# moire_v1_7.net
KiCad netlist of a schematic drawn in EAGLE
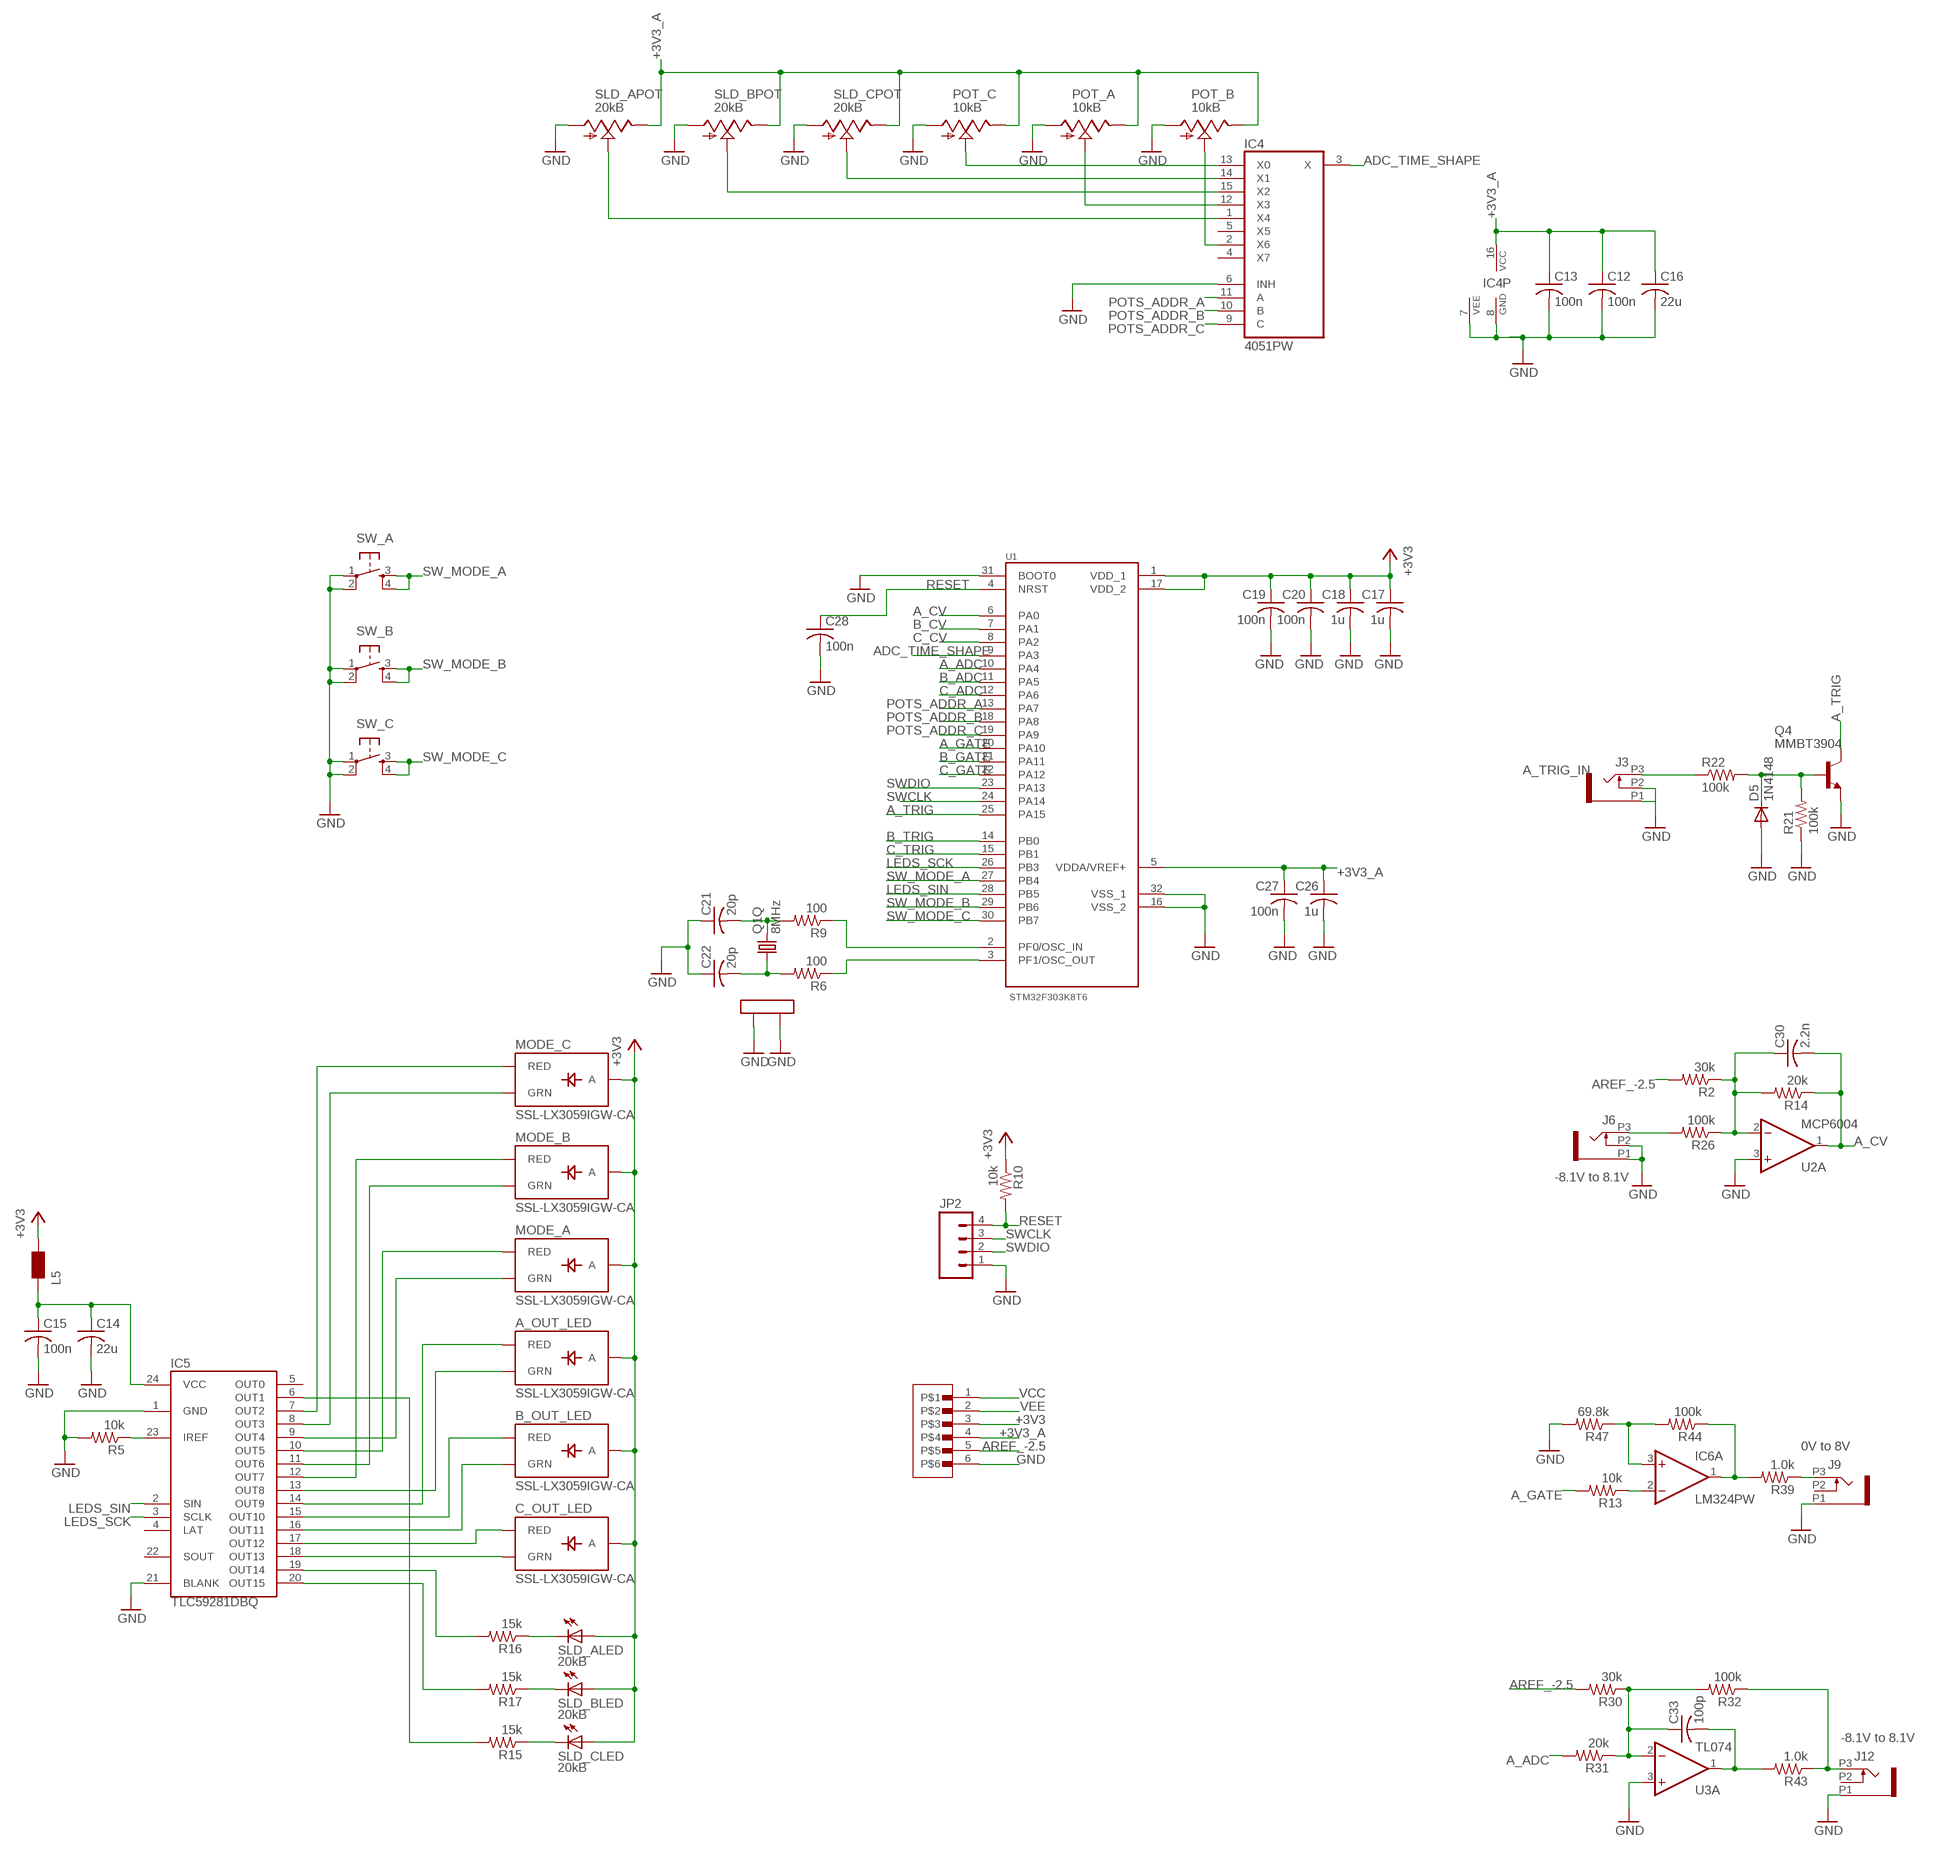
[diagram p0: schematic, sheet 1, part 1 of 2]
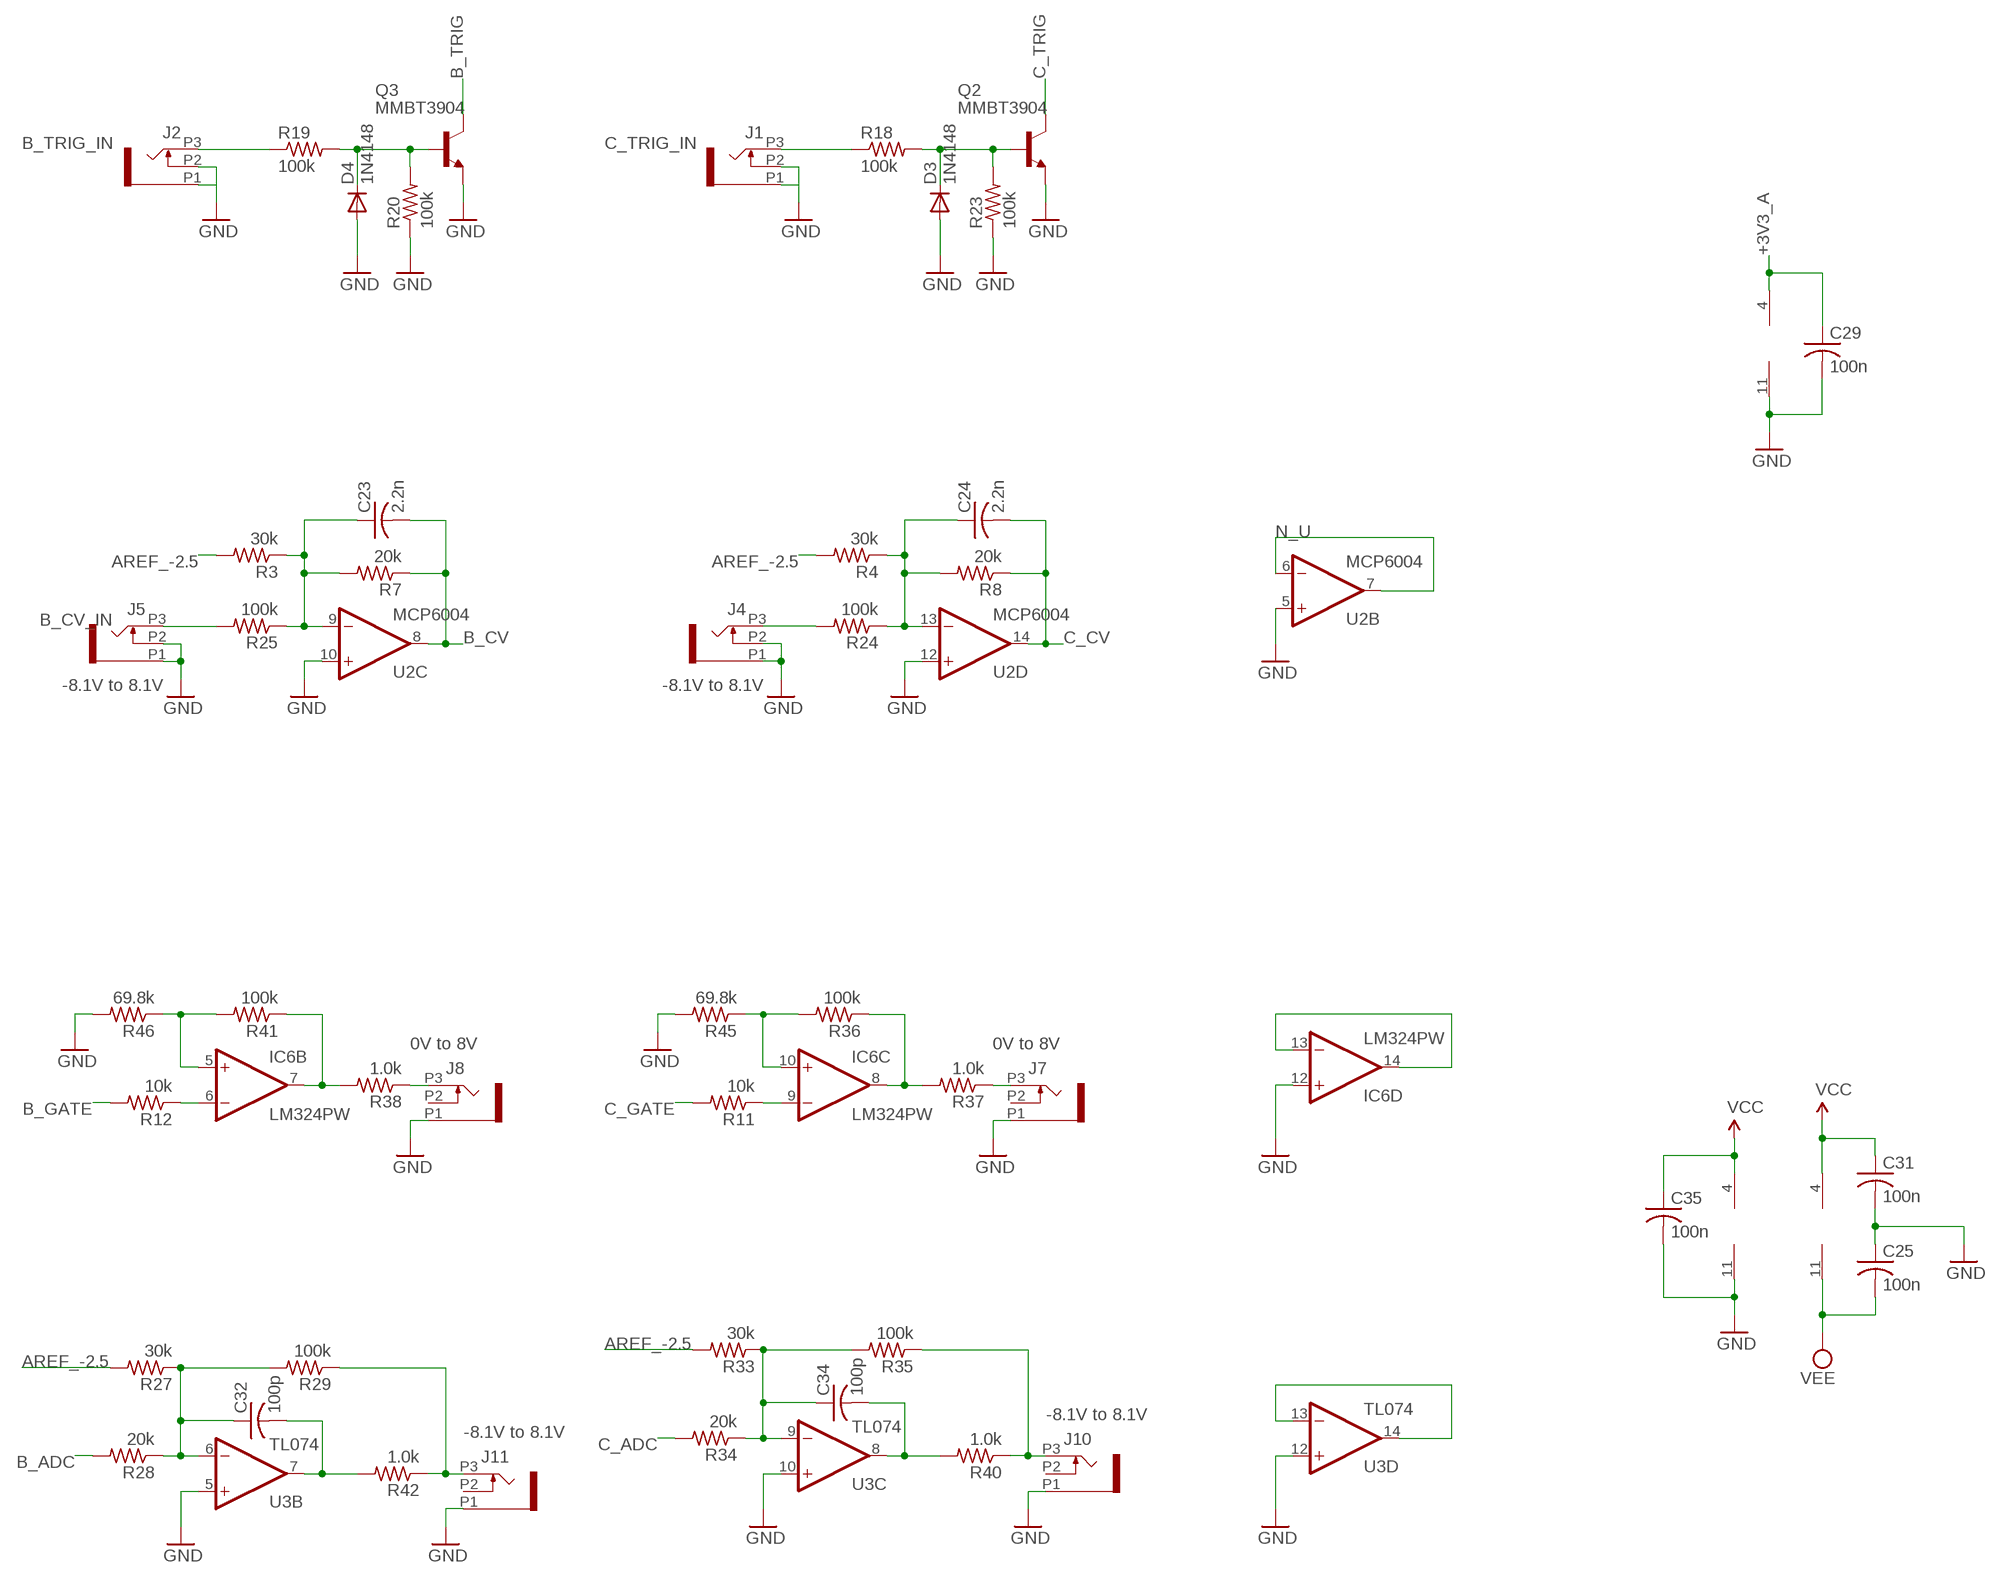
[diagram p1: schematic, sheet 1, part 2 of 2]
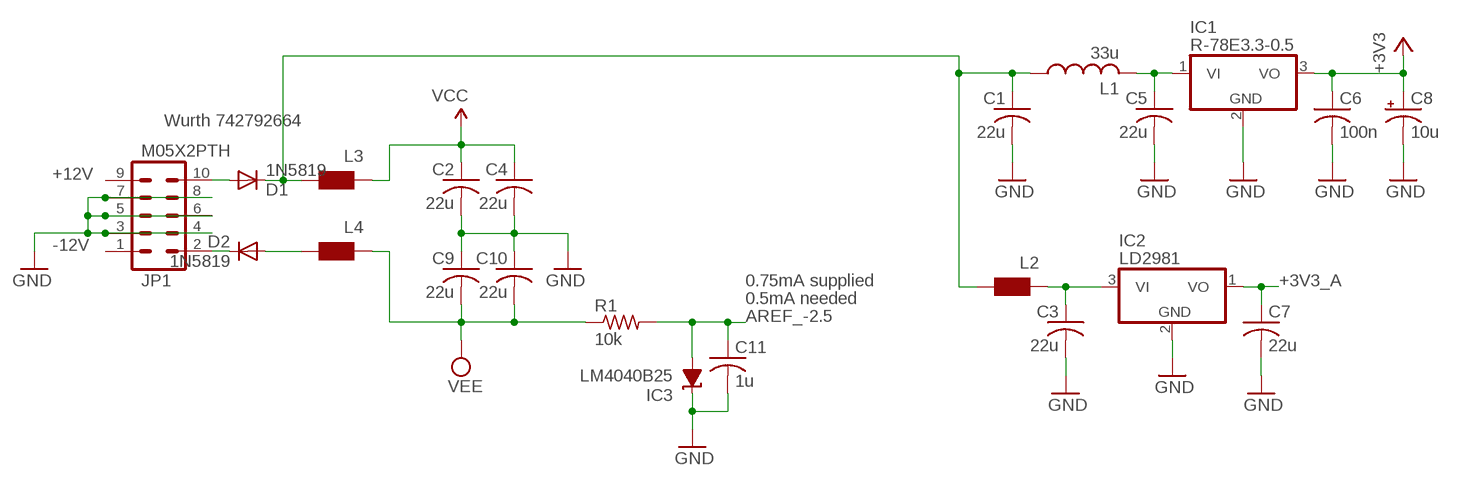
[diagram p2: schematic, sheet 2]

(export (version "E")
  (design (tool "Eeschema 10.0.6"))
  (components
    (comp (ref "C1")
      (value "22u")
      (footprint "eagle-import:RCL_C1206")
      (libsource (lib "eagle-import") (part "RCL_C-USC1206"))
    )
    (comp (ref "C2")
      (value "22u")
      (footprint "eagle-import:RCL_C1206")
      (libsource (lib "eagle-import") (part "RCL_C-USC1206"))
    )
    (comp (ref "C3")
      (value "22u")
      (footprint "eagle-import:RCL_C1206")
      (libsource (lib "eagle-import") (part "RCL_C-USC1206"))
    )
    (comp (ref "C4")
      (value "22u")
      (footprint "eagle-import:RCL_C1206")
      (libsource (lib "eagle-import") (part "RCL_C-USC1206"))
    )
    (comp (ref "C5")
      (value "22u")
      (footprint "eagle-import:RCL_C1206")
      (libsource (lib "eagle-import") (part "RCL_C-USC1206"))
    )
    (comp (ref "C6")
      (value "100n")
      (footprint "eagle-import:RCL_C0603")
      (libsource (lib "eagle-import") (part "RCL_C-USC0603"))
    )
    (comp (ref "C7")
      (value "22u")
      (footprint "eagle-import:RCL_C1206")
      (libsource (lib "eagle-import") (part "RCL_C-USC1206"))
    )
    (comp (ref "C8")
      (value "10u")
      (footprint "eagle-import:RCL_PANASONIC_A")
      (libsource (lib "eagle-import") (part "RCL_CPOL-USA"))
    )
    (comp (ref "C9")
      (value "22u")
      (footprint "eagle-import:RCL_C1206")
      (libsource (lib "eagle-import") (part "RCL_C-USC1206"))
    )
    (comp (ref "C10")
      (value "22u")
      (footprint "eagle-import:RCL_C1206")
      (libsource (lib "eagle-import") (part "RCL_C-USC1206"))
    )
    (comp (ref "C11")
      (value "1u")
      (footprint "eagle-import:RCL_C0603")
      (libsource (lib "eagle-import") (part "RCL_C-USC0603"))
    )
    (comp (ref "D1")
      (value "1N5819")
      (footprint "eagle-import:SOD123")
      (libsource (lib "eagle-import") (part "DIODE-SOD123"))
    )
    (comp (ref "D2")
      (value "1N5819")
      (footprint "eagle-import:SOD123")
      (libsource (lib "eagle-import") (part "DIODE-SOD123"))
    )
    (comp (ref "IC1")
      (value "R-78E3.3-0.5")
      (footprint "eagle-import:WE78")
      (libsource (lib "eagle-import") (part "WE173950378"))
    )
    (comp (ref "IC2")
      (value "LD2981")
      (footprint "eagle-import:SOT89")
      (libsource (lib "eagle-import") (part "LD2981ABU"))
    )
    (comp (ref "IC3")
      (value "LM4040B25")
      (footprint "eagle-import:DBZ_R-PDSO-G3")
      (libsource (lib "eagle-import") (part "LM4041DBZB12"))
    )
    (comp (ref "JP1")
      (value "M05X2PTH")
      (footprint "eagle-import:2X5-PTH")
      (libsource (lib "eagle-import") (part "M05X2PTH"))
    )
    (comp (ref "L1")
      (value "33u")
      (footprint "eagle-import:L2012C")
      (libsource (lib "eagle-import") (part "L-USL2012C"))
    )
    (comp (ref "L2")
      (value "WE-CBF_0603")
      (footprint "eagle-import:0603")
      (libsource (lib "eagle-import") (part "WE-CBF_0603"))
    )
    (comp (ref "L3")
      (value "WE-CBF_0603")
      (footprint "eagle-import:0603")
      (libsource (lib "eagle-import") (part "WE-CBF_0603"))
    )
    (comp (ref "L4")
      (value "WE-CBF_0603")
      (footprint "eagle-import:0603")
      (libsource (lib "eagle-import") (part "WE-CBF_0603"))
    )
    (comp (ref "R1")
      (value "10k")
      (footprint "eagle-import:RCL_R0603")
      (libsource (lib "eagle-import") (part "RCL_R-US_R0603"))
    )
    (comp (ref "A_OUT_LED")
      (value "SSL-LX3059IGW-CA")
      (footprint "eagle-import:LED-BICOLOR-THROUGHHOLE-LUMEX")
      (libsource (lib "eagle-import") (part "LED-BICOLOR-THROUGHHOLE-CA"))
    )
    (comp (ref "B_OUT_LED")
      (value "SSL-LX3059IGW-CA")
      (footprint "eagle-import:LED-BICOLOR-THROUGHHOLE-LUMEX")
      (libsource (lib "eagle-import") (part "LED-BICOLOR-THROUGHHOLE-CA"))
    )
    (comp (ref "C12")
      (value "100n")
      (footprint "eagle-import:RCL_C0603")
      (libsource (lib "eagle-import") (part "RCL_C-USC0603"))
    )
    (comp (ref "C13")
      (value "100n")
      (footprint "eagle-import:RCL_C0603")
      (libsource (lib "eagle-import") (part "RCL_C-USC0603"))
    )
    (comp (ref "C14")
      (value "22u")
      (footprint "eagle-import:RCL_C1206")
      (libsource (lib "eagle-import") (part "RCL_C-USC1206"))
    )
    (comp (ref "C15")
      (value "100n")
      (footprint "eagle-import:RCL_C0603")
      (libsource (lib "eagle-import") (part "RCL_C-USC0603"))
    )
    (comp (ref "C16")
      (value "22u")
      (footprint "eagle-import:RCL_C1206")
      (libsource (lib "eagle-import") (part "RCL_C-USC1206"))
    )
    (comp (ref "C17")
      (value "1u")
      (footprint "eagle-import:RCL_C0603")
      (libsource (lib "eagle-import") (part "RCL_C-USC0603"))
    )
    (comp (ref "C18")
      (value "1u")
      (footprint "eagle-import:RCL_C0603")
      (libsource (lib "eagle-import") (part "RCL_C-USC0603"))
    )
    (comp (ref "C19")
      (value "100n")
      (footprint "eagle-import:RCL_C0603")
      (libsource (lib "eagle-import") (part "RCL_C-USC0603"))
    )
    (comp (ref "C20")
      (value "100n")
      (footprint "eagle-import:RCL_C0603")
      (libsource (lib "eagle-import") (part "RCL_C-USC0603"))
    )
    (comp (ref "C21")
      (value "20p")
      (footprint "eagle-import:RCL_C0603")
      (libsource (lib "eagle-import") (part "RCL_C-USC0603"))
    )
    (comp (ref "C22")
      (value "20p")
      (footprint "eagle-import:RCL_C0603")
      (libsource (lib "eagle-import") (part "RCL_C-USC0603"))
    )
    (comp (ref "C23")
      (value "2.2n")
      (footprint "eagle-import:RCL_C0603")
      (libsource (lib "eagle-import") (part "RCL_C-USC0603"))
    )
    (comp (ref "C24")
      (value "2.2n")
      (footprint "eagle-import:RCL_C0603")
      (libsource (lib "eagle-import") (part "RCL_C-USC0603"))
    )
    (comp (ref "C25")
      (value "100n")
      (footprint "eagle-import:RCL_C0603")
      (libsource (lib "eagle-import") (part "RCL_C-USC0603"))
    )
    (comp (ref "C26")
      (value "1u")
      (footprint "eagle-import:RCL_C0603")
      (libsource (lib "eagle-import") (part "RCL_C-USC0603"))
    )
    (comp (ref "C27")
      (value "100n")
      (footprint "eagle-import:RCL_C0603")
      (libsource (lib "eagle-import") (part "RCL_C-USC0603"))
    )
    (comp (ref "C28")
      (value "100n")
      (footprint "eagle-import:RCL_C0603")
      (libsource (lib "eagle-import") (part "RCL_C-USC0603"))
    )
    (comp (ref "C29")
      (value "100n")
      (footprint "eagle-import:RCL_C0603")
      (libsource (lib "eagle-import") (part "RCL_C-USC0603"))
    )
    (comp (ref "C30")
      (value "2.2n")
      (footprint "eagle-import:RCL_C0603")
      (libsource (lib "eagle-import") (part "RCL_C-USC0603"))
    )
    (comp (ref "C31")
      (value "100n")
      (footprint "eagle-import:RCL_C0603")
      (libsource (lib "eagle-import") (part "RCL_C-USC0603"))
    )
    (comp (ref "C32")
      (value "100p")
      (footprint "eagle-import:RCL_C0603")
      (libsource (lib "eagle-import") (part "RCL_C-USC0603"))
    )
    (comp (ref "C33")
      (value "100p")
      (footprint "eagle-import:RCL_C0603")
      (libsource (lib "eagle-import") (part "RCL_C-USC0603"))
    )
    (comp (ref "C34")
      (value "100p")
      (footprint "eagle-import:RCL_C0603")
      (libsource (lib "eagle-import") (part "RCL_C-USC0603"))
    )
    (comp (ref "C35")
      (value "100n")
      (footprint "eagle-import:RCL_C0603")
      (libsource (lib "eagle-import") (part "RCL_C-USC0603"))
    )
    (comp (ref "C_OUT_LED")
      (value "SSL-LX3059IGW-CA")
      (footprint "eagle-import:LED-BICOLOR-THROUGHHOLE-LUMEX")
      (libsource (lib "eagle-import") (part "LED-BICOLOR-THROUGHHOLE-CA"))
    )
    (comp (ref "D3")
      (value "1N4148")
      (footprint "eagle-import:SOD523")
      (libsource (lib "eagle-import") (part "DIODE-SOD523"))
    )
    (comp (ref "D4")
      (value "1N4148")
      (footprint "eagle-import:SOD523")
      (libsource (lib "eagle-import") (part "DIODE-SOD523"))
    )
    (comp (ref "D5")
      (value "1N4148")
      (footprint "eagle-import:SOD523")
      (libsource (lib "eagle-import") (part "DIODE-SOD523"))
    )
    (comp (ref "IC4")
      (value "4051PW")
      (footprint "eagle-import:TSSOP16_065")
      (libsource (lib "eagle-import") (part "4051PW"))
    )
    (comp (ref "IC5")
      (value "TLC59281DBQ")
      (footprint "eagle-import:TSSOP24_0635")
      (libsource (lib "eagle-import") (part "TLC59281DBQ"))
    )
    (comp (ref "IC6")
      (value "LM324PW")
      (footprint "eagle-import:TSSOP14_065")
      (libsource (lib "eagle-import") (part "TL074PW"))
    )
    (comp (ref "J1")
      (value "PJ301_THONKICONN6")
      (footprint "eagle-import:WQP_PJ_301M6")
      (libsource (lib "eagle-import") (part "PJ301_THONKICONN6"))
    )
    (comp (ref "J2")
      (value "PJ301_THONKICONN6")
      (footprint "eagle-import:WQP_PJ_301M6")
      (libsource (lib "eagle-import") (part "PJ301_THONKICONN6"))
    )
    (comp (ref "J3")
      (value "PJ301_THONKICONN6")
      (footprint "eagle-import:WQP_PJ_301M6")
      (libsource (lib "eagle-import") (part "PJ301_THONKICONN6"))
    )
    (comp (ref "J4")
      (value "PJ301_THONKICONN6")
      (footprint "eagle-import:WQP_PJ_301M6")
      (libsource (lib "eagle-import") (part "PJ301_THONKICONN6"))
    )
    (comp (ref "J5")
      (value "PJ301_THONKICONN6")
      (footprint "eagle-import:WQP_PJ_301M6")
      (libsource (lib "eagle-import") (part "PJ301_THONKICONN6"))
    )
    (comp (ref "J6")
      (value "PJ301_THONKICONN6")
      (footprint "eagle-import:WQP_PJ_301M6")
      (libsource (lib "eagle-import") (part "PJ301_THONKICONN6"))
    )
    (comp (ref "J7")
      (value "PJ301_THONKICONN6")
      (footprint "eagle-import:WQP_PJ_301M6")
      (libsource (lib "eagle-import") (part "PJ301_THONKICONN6"))
    )
    (comp (ref "J8")
      (value "PJ301_THONKICONN6")
      (footprint "eagle-import:WQP_PJ_301M6")
      (libsource (lib "eagle-import") (part "PJ301_THONKICONN6"))
    )
    (comp (ref "J9")
      (value "PJ301_THONKICONN6")
      (footprint "eagle-import:WQP_PJ_301M6")
      (libsource (lib "eagle-import") (part "PJ301_THONKICONN6"))
    )
    (comp (ref "J10")
      (value "PJ301_THONKICONN6")
      (footprint "eagle-import:WQP_PJ_301M6")
      (libsource (lib "eagle-import") (part "PJ301_THONKICONN6"))
    )
    (comp (ref "J11")
      (value "PJ301_THONKICONN6")
      (footprint "eagle-import:WQP_PJ_301M6")
      (libsource (lib "eagle-import") (part "PJ301_THONKICONN6"))
    )
    (comp (ref "J12")
      (value "PJ301_THONKICONN6")
      (footprint "eagle-import:WQP_PJ_301M6")
      (libsource (lib "eagle-import") (part "PJ301_THONKICONN6"))
    )
    (comp (ref "JP2")
      (value "M04PTH")
      (footprint "eagle-import:1X04")
      (libsource (lib "eagle-import") (part "M04PTH"))
    )
    (comp (ref "L5")
      (value "WE-CBF_0603")
      (footprint "eagle-import:0603")
      (libsource (lib "eagle-import") (part "WE-CBF_0603"))
    )
    (comp (ref "MODE_A")
      (value "SSL-LX3059IGW-CA")
      (footprint "eagle-import:LED-BICOLOR-THROUGHHOLE-LUMEX")
      (libsource (lib "eagle-import") (part "LED-BICOLOR-THROUGHHOLE-CA"))
    )
    (comp (ref "MODE_B")
      (value "SSL-LX3059IGW-CA")
      (footprint "eagle-import:LED-BICOLOR-THROUGHHOLE-LUMEX")
      (libsource (lib "eagle-import") (part "LED-BICOLOR-THROUGHHOLE-CA"))
    )
    (comp (ref "MODE_C")
      (value "SSL-LX3059IGW-CA")
      (footprint "eagle-import:LED-BICOLOR-THROUGHHOLE-LUMEX")
      (libsource (lib "eagle-import") (part "LED-BICOLOR-THROUGHHOLE-CA"))
    )
    (comp (ref "POT_A")
      (value "10kB")
      (footprint "eagle-import:ALPS_POT_VERTICAL")
      (libsource (lib "eagle-import") (part "POT_USVERTICAL"))
    )
    (comp (ref "POT_B")
      (value "10kB")
      (footprint "eagle-import:ALPS_POT_VERTICAL")
      (libsource (lib "eagle-import") (part "POT_USVERTICAL"))
    )
    (comp (ref "POT_C")
      (value "10kB")
      (footprint "eagle-import:ALPS_POT_VERTICAL")
      (libsource (lib "eagle-import") (part "POT_USVERTICAL"))
    )
    (comp (ref "Q1")
      (value "8MHz")
      (footprint "eagle-import:CTS406")
      (libsource (lib "eagle-import") (part "CRYSTAL"))
    )
    (comp (ref "Q2")
      (value "MMBT3904")
      (footprint "eagle-import:SOT23-BEC")
      (libsource (lib "eagle-import") (part "-NPN-SOT23-BECMMBT3904LT1"))
    )
    (comp (ref "Q3")
      (value "MMBT3904")
      (footprint "eagle-import:SOT23-BEC")
      (libsource (lib "eagle-import") (part "-NPN-SOT23-BECMMBT3904LT1"))
    )
    (comp (ref "Q4")
      (value "MMBT3904")
      (footprint "eagle-import:SOT23-BEC")
      (libsource (lib "eagle-import") (part "-NPN-SOT23-BECMMBT3904LT1"))
    )
    (comp (ref "R2")
      (value "30k")
      (footprint "eagle-import:RCL_R0603")
      (libsource (lib "eagle-import") (part "RCL_R-US_R0603"))
    )
    (comp (ref "R3")
      (value "30k")
      (footprint "eagle-import:RCL_R0603")
      (libsource (lib "eagle-import") (part "RCL_R-US_R0603"))
    )
    (comp (ref "R4")
      (value "30k")
      (footprint "eagle-import:RCL_R0603")
      (libsource (lib "eagle-import") (part "RCL_R-US_R0603"))
    )
    (comp (ref "R5")
      (value "10k")
      (footprint "eagle-import:RCL_R0603")
      (libsource (lib "eagle-import") (part "RCL_R-US_R0603"))
    )
    (comp (ref "R6")
      (value "100")
      (footprint "eagle-import:RCL_R0603")
      (libsource (lib "eagle-import") (part "RCL_R-US_R0603"))
    )
    (comp (ref "R7")
      (value "20k")
      (footprint "eagle-import:RCL_R0603")
      (libsource (lib "eagle-import") (part "RCL_R-US_R0603"))
    )
    (comp (ref "R8")
      (value "20k")
      (footprint "eagle-import:RCL_R0603")
      (libsource (lib "eagle-import") (part "RCL_R-US_R0603"))
    )
    (comp (ref "R9")
      (value "100")
      (footprint "eagle-import:RCL_R0603")
      (libsource (lib "eagle-import") (part "RCL_R-US_R0603"))
    )
    (comp (ref "R10")
      (value "10k")
      (footprint "eagle-import:RCL_R0603")
      (libsource (lib "eagle-import") (part "RCL_R-US_R0603"))
    )
    (comp (ref "R11")
      (value "10k")
      (footprint "eagle-import:RCL_R0603")
      (libsource (lib "eagle-import") (part "RCL_R-US_R0603"))
    )
    (comp (ref "R12")
      (value "10k")
      (footprint "eagle-import:RCL_R0603")
      (libsource (lib "eagle-import") (part "RCL_R-US_R0603"))
    )
    (comp (ref "R13")
      (value "10k")
      (footprint "eagle-import:RCL_R0603")
      (libsource (lib "eagle-import") (part "RCL_R-US_R0603"))
    )
    (comp (ref "R14")
      (value "20k")
      (footprint "eagle-import:RCL_R0603")
      (libsource (lib "eagle-import") (part "RCL_R-US_R0603"))
    )
    (comp (ref "R15")
      (value "15k")
      (footprint "eagle-import:RCL_R0603")
      (libsource (lib "eagle-import") (part "RCL_R-US_R0603"))
    )
    (comp (ref "R16")
      (value "15k")
      (footprint "eagle-import:RCL_R0603")
      (libsource (lib "eagle-import") (part "RCL_R-US_R0603"))
    )
    (comp (ref "R17")
      (value "15k")
      (footprint "eagle-import:RCL_R0603")
      (libsource (lib "eagle-import") (part "RCL_R-US_R0603"))
    )
    (comp (ref "R18")
      (value "100k")
      (footprint "eagle-import:RCL_R0603")
      (libsource (lib "eagle-import") (part "RCL_R-US_R0603"))
    )
    (comp (ref "R19")
      (value "100k")
      (footprint "eagle-import:RCL_R0603")
      (libsource (lib "eagle-import") (part "RCL_R-US_R0603"))
    )
    (comp (ref "R20")
      (value "100k")
      (footprint "eagle-import:RCL_R0603")
      (libsource (lib "eagle-import") (part "RCL_R-US_R0603"))
    )
    (comp (ref "R21")
      (value "100k")
      (footprint "eagle-import:RCL_R0603")
      (libsource (lib "eagle-import") (part "RCL_R-US_R0603"))
    )
    (comp (ref "R22")
      (value "100k")
      (footprint "eagle-import:RCL_R0603")
      (libsource (lib "eagle-import") (part "RCL_R-US_R0603"))
    )
    (comp (ref "R23")
      (value "100k")
      (footprint "eagle-import:RCL_R0603")
      (libsource (lib "eagle-import") (part "RCL_R-US_R0603"))
    )
    (comp (ref "R24")
      (value "100k")
      (footprint "eagle-import:RCL_R0603")
      (libsource (lib "eagle-import") (part "RCL_R-US_R0603"))
    )
    (comp (ref "R25")
      (value "100k")
      (footprint "eagle-import:RCL_R0603")
      (libsource (lib "eagle-import") (part "RCL_R-US_R0603"))
    )
    (comp (ref "R26")
      (value "100k")
      (footprint "eagle-import:RCL_R0603")
      (libsource (lib "eagle-import") (part "RCL_R-US_R0603"))
    )
    (comp (ref "R27")
      (value "30k")
      (footprint "eagle-import:RCL_R0603")
      (libsource (lib "eagle-import") (part "RCL_R-US_R0603"))
    )
    (comp (ref "R28")
      (value "20k")
      (footprint "eagle-import:RCL_R0603")
      (libsource (lib "eagle-import") (part "RCL_R-US_R0603"))
    )
    (comp (ref "R29")
      (value "100k")
      (footprint "eagle-import:RCL_R0603")
      (libsource (lib "eagle-import") (part "RCL_R-US_R0603"))
    )
    (comp (ref "R30")
      (value "30k")
      (footprint "eagle-import:RCL_R0603")
      (libsource (lib "eagle-import") (part "RCL_R-US_R0603"))
    )
    (comp (ref "R31")
      (value "20k")
      (footprint "eagle-import:RCL_R0603")
      (libsource (lib "eagle-import") (part "RCL_R-US_R0603"))
    )
    (comp (ref "R32")
      (value "100k")
      (footprint "eagle-import:RCL_R0603")
      (libsource (lib "eagle-import") (part "RCL_R-US_R0603"))
    )
    (comp (ref "R33")
      (value "30k")
      (footprint "eagle-import:RCL_R0603")
      (libsource (lib "eagle-import") (part "RCL_R-US_R0603"))
    )
    (comp (ref "R34")
      (value "20k")
      (footprint "eagle-import:RCL_R0603")
      (libsource (lib "eagle-import") (part "RCL_R-US_R0603"))
    )
    (comp (ref "R35")
      (value "100k")
      (footprint "eagle-import:RCL_R0603")
      (libsource (lib "eagle-import") (part "RCL_R-US_R0603"))
    )
    (comp (ref "R36")
      (value "100k")
      (footprint "eagle-import:RCL_R0603")
      (libsource (lib "eagle-import") (part "RCL_R-US_R0603"))
    )
    (comp (ref "R37")
      (value "1.0k")
      (footprint "eagle-import:RCL_R0603")
      (libsource (lib "eagle-import") (part "RCL_R-US_R0603"))
    )
    (comp (ref "R38")
      (value "1.0k")
      (footprint "eagle-import:RCL_R0603")
      (libsource (lib "eagle-import") (part "RCL_R-US_R0603"))
    )
    (comp (ref "R39")
      (value "1.0k")
      (footprint "eagle-import:RCL_R0603")
      (libsource (lib "eagle-import") (part "RCL_R-US_R0603"))
    )
    (comp (ref "R40")
      (value "1.0k")
      (footprint "eagle-import:RCL_R0603")
      (libsource (lib "eagle-import") (part "RCL_R-US_R0603"))
    )
    (comp (ref "R41")
      (value "100k")
      (footprint "eagle-import:RCL_R0603")
      (libsource (lib "eagle-import") (part "RCL_R-US_R0603"))
    )
    (comp (ref "R42")
      (value "1.0k")
      (footprint "eagle-import:RCL_R0603")
      (libsource (lib "eagle-import") (part "RCL_R-US_R0603"))
    )
    (comp (ref "R43")
      (value "1.0k")
      (footprint "eagle-import:RCL_R0603")
      (libsource (lib "eagle-import") (part "RCL_R-US_R0603"))
    )
    (comp (ref "R44")
      (value "100k")
      (footprint "eagle-import:RCL_R0603")
      (libsource (lib "eagle-import") (part "RCL_R-US_R0603"))
    )
    (comp (ref "R45")
      (value "69.8k")
      (footprint "eagle-import:RCL_R0603")
      (libsource (lib "eagle-import") (part "RCL_R-US_R0603"))
    )
    (comp (ref "R46")
      (value "69.8k")
      (footprint "eagle-import:RCL_R0603")
      (libsource (lib "eagle-import") (part "RCL_R-US_R0603"))
    )
    (comp (ref "R47")
      (value "69.8k")
      (footprint "eagle-import:RCL_R0603")
      (libsource (lib "eagle-import") (part "RCL_R-US_R0603"))
    )
    (comp (ref "SLD_A")
      (value "20kB")
      (footprint "eagle-import:BOURNS_SLIDER")
      (libsource (lib "eagle-import") (part "BOURNS_SLIDER"))
    )
    (comp (ref "SLD_B")
      (value "20kB")
      (footprint "eagle-import:BOURNS_SLIDER")
      (libsource (lib "eagle-import") (part "BOURNS_SLIDER"))
    )
    (comp (ref "SLD_C")
      (value "20kB")
      (footprint "eagle-import:BOURNS_SLIDER")
      (libsource (lib "eagle-import") (part "BOURNS_SLIDER"))
    )
    (comp (ref "SW_A")
      (value "TAC_SWITCHPTH")
      (footprint "eagle-import:TACTILE-PTH")
      (libsource (lib "eagle-import") (part "TAC_SWITCHPTH"))
    )
    (comp (ref "SW_B")
      (value "TAC_SWITCHPTH")
      (footprint "eagle-import:TACTILE-PTH")
      (libsource (lib "eagle-import") (part "TAC_SWITCHPTH"))
    )
    (comp (ref "SW_C")
      (value "TAC_SWITCHPTH")
      (footprint "eagle-import:TACTILE-PTH")
      (libsource (lib "eagle-import") (part "TAC_SWITCHPTH"))
    )
    (comp (ref "U$1")
      (value "1X6-SMD-TESTPAD")
      (footprint "eagle-import:6X1-SMD-TESTPAD")
      (libsource (lib "eagle-import") (part "1X6-SMD-TESTPAD"))
    )
    (comp (ref "U1")
      (value "STM32F303K8T6")
      (footprint "eagle-import:QFP80P900X900X160-32N")
      (fields (field (name "MF") "STMicroelectronics"))
      (libsource (lib "eagle-import") (part "STM32F303K8T6"))
    )
    (comp (ref "U2")
      (value "MCP6004")
      (footprint "eagle-import:SO14")
      (libsource (lib "eagle-import") (part "MCP6004_SMD"))
    )
    (comp (ref "U3")
      (value "TL074")
      (footprint "eagle-import:SO14")
      (libsource (lib "eagle-import") (part "TL074_SMD"))
    )
  )
  (nets
    (net (code "1") (name "+3V3") (class "Default")
      (node (ref "A_OUT_LED") (pin "A") (pinfunction "A_A") (pintype "bidirectional"))
      (node (ref "B_OUT_LED") (pin "A") (pinfunction "A_A") (pintype "bidirectional"))
      (node (ref "C17") (pin "1") (pinfunction "1_1") (pintype "passive"))
      (node (ref "C18") (pin "1") (pinfunction "1_1") (pintype "passive"))
      (node (ref "C19") (pin "1") (pinfunction "1_1") (pintype "passive"))
      (node (ref "C20") (pin "1") (pinfunction "1_1") (pintype "passive"))
      (node (ref "C6") (pin "1") (pinfunction "1_1") (pintype "passive"))
      (node (ref "C8") (pin "+") (pinfunction "+_+") (pintype "passive"))
      (node (ref "C_OUT_LED") (pin "A") (pinfunction "A_A") (pintype "bidirectional"))
      (node (ref "IC1") (pin "3") (pinfunction "VO_3") (pintype "passive"))
      (node (ref "L5") (pin "2") (pinfunction "2_2") (pintype "passive"))
      (node (ref "MODE_A") (pin "A") (pinfunction "A_A") (pintype "bidirectional"))
      (node (ref "MODE_B") (pin "A") (pinfunction "A_A") (pintype "bidirectional"))
      (node (ref "MODE_C") (pin "A") (pinfunction "A_A") (pintype "bidirectional"))
      (node (ref "R10") (pin "1") (pinfunction "1_1") (pintype "passive"))
      (node (ref "SLD_A") (pin "B") (pinfunction "A_B") (pintype "passive"))
      (node (ref "SLD_B") (pin "B") (pinfunction "A_B") (pintype "passive"))
      (node (ref "SLD_C") (pin "B") (pinfunction "A_B") (pintype "passive"))
      (node (ref "U$1") (pin "3") (pinfunction "P$3_3") (pintype "bidirectional"))
      (node (ref "U1") (pin "1") (pinfunction "VDD_1_1") (pintype "power_in"))
      (node (ref "U1") (pin "17") (pinfunction "VDD_2_17") (pintype "power_in"))
    )
    (net (code "2") (name "+3V3_A") (class "Default")
      (node (ref "C12") (pin "1") (pinfunction "1_1") (pintype "passive"))
      (node (ref "C13") (pin "1") (pinfunction "1_1") (pintype "passive"))
      (node (ref "C16") (pin "1") (pinfunction "1_1") (pintype "passive"))
      (node (ref "C26") (pin "1") (pinfunction "1_1") (pintype "passive"))
      (node (ref "C27") (pin "1") (pinfunction "1_1") (pintype "passive"))
      (node (ref "C29") (pin "1") (pinfunction "1_1") (pintype "passive"))
      (node (ref "C7") (pin "1") (pinfunction "1_1") (pintype "passive"))
      (node (ref "IC2") (pin "1") (pinfunction "VO_1") (pintype "passive"))
      (node (ref "IC4") (pin "16") (pinfunction "VCC_16") (pintype "power_in"))
      (node (ref "POT_A") (pin "P$1") (pinfunction "E_P$1") (pintype "passive"))
      (node (ref "POT_B") (pin "P$1") (pinfunction "E_P$1") (pintype "passive"))
      (node (ref "POT_C") (pin "P$1") (pinfunction "E_P$1") (pintype "passive"))
      (node (ref "SLD_A") (pin "3") (pinfunction "E_3") (pintype "passive"))
      (node (ref "SLD_B") (pin "3") (pinfunction "E_3") (pintype "passive"))
      (node (ref "SLD_C") (pin "3") (pinfunction "E_3") (pintype "passive"))
      (node (ref "U$1") (pin "4") (pinfunction "P$4_4") (pintype "bidirectional"))
      (node (ref "U1") (pin "5") (pinfunction "VDDA/VREF+_5") (pintype "power_in"))
      (node (ref "U2") (pin "4") (pinfunction "V+_4") (pintype "power_in"))
    )
    (net (code "3") (name "+12V") (class "Default")
      (node (ref "D1") (pin "A") (pinfunction "A_A") (pintype "passive"))
      (node (ref "JP1") (pin "10") (pinfunction "10_10") (pintype "passive"))
      (node (ref "JP1") (pin "9") (pinfunction "9_9") (pintype "passive"))
    )
    (net (code "4") (name "-12V") (class "Default")
      (node (ref "D2") (pin "C") (pinfunction "C_C") (pintype "passive"))
      (node (ref "JP1") (pin "1") (pinfunction "1_1") (pintype "passive"))
      (node (ref "JP1") (pin "2") (pinfunction "2_2") (pintype "passive"))
    )
    (net (code "5") (name "ADC_TIME_SHAPE") (class "Default")
      (node (ref "IC4") (pin "3") (pinfunction "X_3") (pintype "bidirectional"))
      (node (ref "U1") (pin "9") (pinfunction "PA3_9") (pintype "bidirectional"))
    )
    (net (code "6") (name "AREF_-2.5") (class "Default")
      (node (ref "C11") (pin "1") (pinfunction "1_1") (pintype "passive"))
      (node (ref "IC3") (pin "2") (pinfunction "A_2") (pintype "passive"))
      (node (ref "R1") (pin "2") (pinfunction "2_2") (pintype "passive"))
      (node (ref "R2") (pin "2") (pinfunction "2_2") (pintype "passive"))
      (node (ref "R27") (pin "2") (pinfunction "2_2") (pintype "passive"))
      (node (ref "R3") (pin "2") (pinfunction "2_2") (pintype "passive"))
      (node (ref "R30") (pin "2") (pinfunction "2_2") (pintype "passive"))
      (node (ref "R33") (pin "2") (pinfunction "2_2") (pintype "passive"))
      (node (ref "R4") (pin "2") (pinfunction "2_2") (pintype "passive"))
      (node (ref "U$1") (pin "5") (pinfunction "P$5_5") (pintype "bidirectional"))
    )
    (net (code "7") (name "A_ADC") (class "Default")
      (node (ref "R31") (pin "2") (pinfunction "2_2") (pintype "passive"))
      (node (ref "U1") (pin "10") (pinfunction "PA4_10") (pintype "bidirectional"))
    )
    (net (code "8") (name "A_CV") (class "Default")
      (node (ref "C30") (pin "2") (pinfunction "2_2") (pintype "passive"))
      (node (ref "R14") (pin "1") (pinfunction "1_1") (pintype "passive"))
      (node (ref "U1") (pin "6") (pinfunction "PA0_6") (pintype "bidirectional"))
      (node (ref "U2") (pin "1") (pinfunction "OUT_1") (pintype "output"))
    )
    (net (code "9") (name "A_GATE") (class "Default")
      (node (ref "R13") (pin "2") (pinfunction "2_2") (pintype "passive"))
      (node (ref "U1") (pin "20") (pinfunction "PA10_20") (pintype "bidirectional"))
    )
    (net (code "10") (name "A_TRIG") (class "Default")
      (node (ref "Q4") (pin "C") (pinfunction "C_C") (pintype "passive"))
      (node (ref "U1") (pin "25") (pinfunction "PA15_25") (pintype "bidirectional"))
    )
    (net (code "11") (name "A_TRIG_IN") (class "Default")
      (node (ref "J3") (pin "P3") (pinfunction "3_P3") (pintype "passive"))
      (node (ref "R22") (pin "1") (pinfunction "1_1") (pintype "passive"))
    )
    (net (code "12") (name "B_ADC") (class "Default")
      (node (ref "R28") (pin "2") (pinfunction "2_2") (pintype "passive"))
      (node (ref "U1") (pin "11") (pinfunction "PA5_11") (pintype "bidirectional"))
    )
    (net (code "13") (name "B_CV") (class "Default")
      (node (ref "C23") (pin "2") (pinfunction "2_2") (pintype "passive"))
      (node (ref "R7") (pin "1") (pinfunction "1_1") (pintype "passive"))
      (node (ref "U1") (pin "7") (pinfunction "PA1_7") (pintype "bidirectional"))
      (node (ref "U2") (pin "8") (pinfunction "OUT_8") (pintype "output"))
    )
    (net (code "14") (name "B_CV_IN") (class "Default")
      (node (ref "J5") (pin "P3") (pinfunction "3_P3") (pintype "passive"))
      (node (ref "R25") (pin "2") (pinfunction "2_2") (pintype "passive"))
    )
    (net (code "15") (name "B_GATE") (class "Default")
      (node (ref "R12") (pin "2") (pinfunction "2_2") (pintype "passive"))
      (node (ref "U1") (pin "21") (pinfunction "PA11_21") (pintype "bidirectional"))
    )
    (net (code "16") (name "B_TRIG") (class "Default")
      (node (ref "Q3") (pin "C") (pinfunction "C_C") (pintype "passive"))
      (node (ref "U1") (pin "14") (pinfunction "PB0_14") (pintype "bidirectional"))
    )
    (net (code "17") (name "B_TRIG_IN") (class "Default")
      (node (ref "J2") (pin "P3") (pinfunction "3_P3") (pintype "passive"))
      (node (ref "R19") (pin "1") (pinfunction "1_1") (pintype "passive"))
    )
    (net (code "18") (name "C_ADC") (class "Default")
      (node (ref "R34") (pin "2") (pinfunction "2_2") (pintype "passive"))
      (node (ref "U1") (pin "12") (pinfunction "PA6_12") (pintype "bidirectional"))
    )
    (net (code "19") (name "C_CV") (class "Default")
      (node (ref "C24") (pin "2") (pinfunction "2_2") (pintype "passive"))
      (node (ref "R8") (pin "1") (pinfunction "1_1") (pintype "passive"))
      (node (ref "U1") (pin "8") (pinfunction "PA2_8") (pintype "bidirectional"))
      (node (ref "U2") (pin "14") (pinfunction "OUT_14") (pintype "output"))
    )
    (net (code "20") (name "C_GATE") (class "Default")
      (node (ref "R11") (pin "2") (pinfunction "2_2") (pintype "passive"))
      (node (ref "U1") (pin "22") (pinfunction "PA12_22") (pintype "bidirectional"))
    )
    (net (code "21") (name "C_TRIG") (class "Default")
      (node (ref "Q2") (pin "C") (pinfunction "C_C") (pintype "passive"))
      (node (ref "U1") (pin "15") (pinfunction "PB1_15") (pintype "bidirectional"))
    )
    (net (code "22") (name "C_TRIG_IN") (class "Default")
      (node (ref "J1") (pin "P3") (pinfunction "3_P3") (pintype "passive"))
      (node (ref "R18") (pin "1") (pinfunction "1_1") (pintype "passive"))
    )
    (net (code "23") (name "GND") (class "Default")
      (node (ref "C1") (pin "2") (pinfunction "2_2") (pintype "passive"))
      (node (ref "C10") (pin "1") (pinfunction "1_1") (pintype "passive"))
      (node (ref "C11") (pin "2") (pinfunction "2_2") (pintype "passive"))
      (node (ref "C12") (pin "2") (pinfunction "2_2") (pintype "passive"))
      (node (ref "C13") (pin "2") (pinfunction "2_2") (pintype "passive"))
      (node (ref "C14") (pin "2") (pinfunction "2_2") (pintype "passive"))
      (node (ref "C15") (pin "2") (pinfunction "2_2") (pintype "passive"))
      (node (ref "C16") (pin "2") (pinfunction "2_2") (pintype "passive"))
      (node (ref "C17") (pin "2") (pinfunction "2_2") (pintype "passive"))
      (node (ref "C18") (pin "2") (pinfunction "2_2") (pintype "passive"))
      (node (ref "C19") (pin "2") (pinfunction "2_2") (pintype "passive"))
      (node (ref "C2") (pin "2") (pinfunction "2_2") (pintype "passive"))
      (node (ref "C20") (pin "2") (pinfunction "2_2") (pintype "passive"))
      (node (ref "C21") (pin "1") (pinfunction "1_1") (pintype "passive"))
      (node (ref "C22") (pin "1") (pinfunction "1_1") (pintype "passive"))
      (node (ref "C25") (pin "1") (pinfunction "1_1") (pintype "passive"))
      (node (ref "C26") (pin "2") (pinfunction "2_2") (pintype "passive"))
      (node (ref "C27") (pin "2") (pinfunction "2_2") (pintype "passive"))
      (node (ref "C28") (pin "2") (pinfunction "2_2") (pintype "passive"))
      (node (ref "C29") (pin "2") (pinfunction "2_2") (pintype "passive"))
      (node (ref "C3") (pin "2") (pinfunction "2_2") (pintype "passive"))
      (node (ref "C31") (pin "2") (pinfunction "2_2") (pintype "passive"))
      (node (ref "C35") (pin "2") (pinfunction "2_2") (pintype "passive"))
      (node (ref "C4") (pin "2") (pinfunction "2_2") (pintype "passive"))
      (node (ref "C5") (pin "2") (pinfunction "2_2") (pintype "passive"))
      (node (ref "C6") (pin "2") (pinfunction "2_2") (pintype "passive"))
      (node (ref "C7") (pin "2") (pinfunction "2_2") (pintype "passive"))
      (node (ref "C8") (pin "-") (pinfunction "-_-") (pintype "passive"))
      (node (ref "C9") (pin "1") (pinfunction "1_1") (pintype "passive"))
      (node (ref "D3") (pin "A") (pinfunction "A_A") (pintype "passive"))
      (node (ref "D4") (pin "A") (pinfunction "A_A") (pintype "passive"))
      (node (ref "D5") (pin "A") (pinfunction "A_A") (pintype "passive"))
      (node (ref "IC1") (pin "2") (pinfunction "GND_2") (pintype "passive"))
      (node (ref "IC2") (pin "2") (pinfunction "GND_2") (pintype "passive"))
      (node (ref "IC3") (pin "1") (pinfunction "C_1") (pintype "passive"))
      (node (ref "IC4") (pin "6") (pinfunction "INH_6") (pintype "input"))
      (node (ref "IC4") (pin "7") (pinfunction "VEE_7") (pintype "power_in"))
      (node (ref "IC4") (pin "8") (pinfunction "GND_8") (pintype "power_in"))
      (node (ref "IC5") (pin "1") (pinfunction "GND_1") (pintype "bidirectional"))
      (node (ref "IC5") (pin "21") (pinfunction "BLANK_21") (pintype "bidirectional"))
      (node (ref "IC6") (pin "11") (pinfunction "V-_11") (pintype "power_in"))
      (node (ref "IC6") (pin "12") (pinfunction "+IN_12") (pintype "input"))
      (node (ref "J1") (pin "P1") (pinfunction "1_P1") (pintype "passive"))
      (node (ref "J1") (pin "P2") (pinfunction "2_P2") (pintype "passive"))
      (node (ref "J10") (pin "P1") (pinfunction "1_P1") (pintype "passive"))
      (node (ref "J11") (pin "P1") (pinfunction "1_P1") (pintype "passive"))
      (node (ref "J12") (pin "P1") (pinfunction "1_P1") (pintype "passive"))
      (node (ref "J2") (pin "P1") (pinfunction "1_P1") (pintype "passive"))
      (node (ref "J2") (pin "P2") (pinfunction "2_P2") (pintype "passive"))
      (node (ref "J3") (pin "P1") (pinfunction "1_P1") (pintype "passive"))
      (node (ref "J3") (pin "P2") (pinfunction "2_P2") (pintype "passive"))
      (node (ref "J4") (pin "P1") (pinfunction "1_P1") (pintype "passive"))
      (node (ref "J4") (pin "P2") (pinfunction "2_P2") (pintype "passive"))
      (node (ref "J5") (pin "P1") (pinfunction "1_P1") (pintype "passive"))
      (node (ref "J5") (pin "P2") (pinfunction "2_P2") (pintype "passive"))
      (node (ref "J6") (pin "P1") (pinfunction "1_P1") (pintype "passive"))
      (node (ref "J6") (pin "P2") (pinfunction "2_P2") (pintype "passive"))
      (node (ref "J7") (pin "P1") (pinfunction "1_P1") (pintype "passive"))
      (node (ref "J8") (pin "P1") (pinfunction "1_P1") (pintype "passive"))
      (node (ref "J9") (pin "P1") (pinfunction "1_P1") (pintype "passive"))
      (node (ref "JP1") (pin "3") (pinfunction "3_3") (pintype "passive"))
      (node (ref "JP1") (pin "4") (pinfunction "4_4") (pintype "passive"))
      (node (ref "JP1") (pin "5") (pinfunction "5_5") (pintype "passive"))
      (node (ref "JP1") (pin "6") (pinfunction "6_6") (pintype "passive"))
      (node (ref "JP1") (pin "7") (pinfunction "7_7") (pintype "passive"))
      (node (ref "JP1") (pin "8") (pinfunction "8_8") (pintype "passive"))
      (node (ref "JP2") (pin "1") (pinfunction "1_1") (pintype "passive"))
      (node (ref "POT_A") (pin "P$3") (pinfunction "A_P$3") (pintype "passive"))
      (node (ref "POT_B") (pin "P$3") (pinfunction "A_P$3") (pintype "passive"))
      (node (ref "POT_C") (pin "P$3") (pinfunction "A_P$3") (pintype "passive"))
      (node (ref "Q1") (pin "2") (pinfunction "LID1_2") (pintype "power_in"))
      (node (ref "Q1") (pin "4") (pinfunction "LID2_4") (pintype "power_in"))
      (node (ref "Q2") (pin "E") (pinfunction "E_E") (pintype "passive"))
      (node (ref "Q3") (pin "E") (pinfunction "E_E") (pintype "passive"))
      (node (ref "Q4") (pin "E") (pinfunction "E_E") (pintype "passive"))
      (node (ref "R20") (pin "1") (pinfunction "1_1") (pintype "passive"))
      (node (ref "R21") (pin "1") (pinfunction "1_1") (pintype "passive"))
      (node (ref "R23") (pin "1") (pinfunction "1_1") (pintype "passive"))
      (node (ref "R45") (pin "2") (pinfunction "2_2") (pintype "passive"))
      (node (ref "R46") (pin "2") (pinfunction "2_2") (pintype "passive"))
      (node (ref "R47") (pin "2") (pinfunction "2_2") (pintype "passive"))
      (node (ref "R5") (pin "2") (pinfunction "2_2") (pintype "passive"))
      (node (ref "SLD_A") (pin "1") (pinfunction "A_1") (pintype "passive"))
      (node (ref "SLD_B") (pin "1") (pinfunction "A_1") (pintype "passive"))
      (node (ref "SLD_C") (pin "1") (pinfunction "A_1") (pintype "passive"))
      (node (ref "SW_A") (pin "1") (pinfunction "1_1") (pintype "passive"))
      (node (ref "SW_A") (pin "2") (pinfunction "2_2") (pintype "passive"))
      (node (ref "SW_B") (pin "1") (pinfunction "1_1") (pintype "passive"))
      (node (ref "SW_B") (pin "2") (pinfunction "2_2") (pintype "passive"))
      (node (ref "SW_C") (pin "1") (pinfunction "1_1") (pintype "passive"))
      (node (ref "SW_C") (pin "2") (pinfunction "2_2") (pintype "passive"))
      (node (ref "U$1") (pin "6") (pinfunction "P$6_6") (pintype "bidirectional"))
      (node (ref "U1") (pin "16") (pinfunction "VSS_2_16") (pintype "power_in"))
      (node (ref "U1") (pin "31") (pinfunction "BOOT0_31") (pintype "input"))
      (node (ref "U1") (pin "32") (pinfunction "VSS_1_32") (pintype "power_in"))
      (node (ref "U2") (pin "10") (pinfunction "+IN_10") (pintype "input"))
      (node (ref "U2") (pin "11") (pinfunction "V-_11") (pintype "power_in"))
      (node (ref "U2") (pin "12") (pinfunction "+IN_12") (pintype "input"))
      (node (ref "U2") (pin "3") (pinfunction "+IN_3") (pintype "input"))
      (node (ref "U2") (pin "5") (pinfunction "+IN_5") (pintype "input"))
      (node (ref "U3") (pin "10") (pinfunction "+IN_10") (pintype "input"))
      (node (ref "U3") (pin "12") (pinfunction "+IN_12") (pintype "input"))
      (node (ref "U3") (pin "3") (pinfunction "+IN_3") (pintype "input"))
      (node (ref "U3") (pin "5") (pinfunction "+IN_5") (pintype "input"))
    )
    (net (code "24") (name "LEDS_SCK") (class "Default")
      (node (ref "IC5") (pin "3") (pinfunction "SCLK_3") (pintype "bidirectional"))
      (node (ref "U1") (pin "26") (pinfunction "PB3_26") (pintype "bidirectional"))
    )
    (net (code "25") (name "LEDS_SIN") (class "Default")
      (node (ref "IC5") (pin "2") (pinfunction "SIN_2") (pintype "bidirectional"))
      (node (ref "U1") (pin "28") (pinfunction "PB5_28") (pintype "bidirectional"))
    )
    (net (code "26") (name "N_U") (class "Default")
      (node (ref "U2") (pin "6") (pinfunction "-IN_6") (pintype "input"))
      (node (ref "U2") (pin "7") (pinfunction "OUT_7") (pintype "output"))
    )
    (net (code "27") (name "Net-(A_OUT_LED-GRN)") (class "Default")
      (node (ref "A_OUT_LED") (pin "GREEN_C") (pinfunction "GRN_GREEN_C") (pintype "bidirectional"))
      (node (ref "IC5") (pin "13") (pinfunction "OUT8_13") (pintype "bidirectional"))
    )
    (net (code "28") (name "Net-(A_OUT_LED-RED)") (class "Default")
      (node (ref "A_OUT_LED") (pin "RED_C") (pinfunction "RED_RED_C") (pintype "bidirectional"))
      (node (ref "IC5") (pin "14") (pinfunction "OUT9_14") (pintype "bidirectional"))
    )
    (net (code "29") (name "Net-(B_OUT_LED-GRN)") (class "Default")
      (node (ref "B_OUT_LED") (pin "GREEN_C") (pinfunction "GRN_GREEN_C") (pintype "bidirectional"))
      (node (ref "IC5") (pin "16") (pinfunction "OUT11_16") (pintype "bidirectional"))
    )
    (net (code "30") (name "Net-(B_OUT_LED-RED)") (class "Default")
      (node (ref "B_OUT_LED") (pin "RED_C") (pinfunction "RED_RED_C") (pintype "bidirectional"))
      (node (ref "IC5") (pin "15") (pinfunction "OUT10_15") (pintype "bidirectional"))
    )
    (net (code "31") (name "Net-(C1-Pad1)") (class "Default")
      (node (ref "C1") (pin "1") (pinfunction "1_1") (pintype "passive"))
      (node (ref "D1") (pin "C") (pinfunction "C_C") (pintype "passive"))
      (node (ref "L1") (pin "1") (pinfunction "1_1") (pintype "passive"))
      (node (ref "L2") (pin "2") (pinfunction "2_2") (pintype "passive"))
      (node (ref "L3") (pin "2") (pinfunction "2_2") (pintype "passive"))
    )
    (net (code "32") (name "Net-(C22-Pad2)") (class "Default")
      (node (ref "C22") (pin "2") (pinfunction "2_2") (pintype "passive"))
      (node (ref "Q1") (pin "1") (pinfunction "1_1") (pintype "passive"))
      (node (ref "R6") (pin "2") (pinfunction "2_2") (pintype "passive"))
    )
    (net (code "33") (name "Net-(C_OUT_LED-GRN)") (class "Default")
      (node (ref "C_OUT_LED") (pin "GREEN_C") (pinfunction "GRN_GREEN_C") (pintype "bidirectional"))
      (node (ref "IC5") (pin "18") (pinfunction "OUT13_18") (pintype "bidirectional"))
    )
    (net (code "34") (name "Net-(C_OUT_LED-RED)") (class "Default")
      (node (ref "C_OUT_LED") (pin "RED_C") (pinfunction "RED_RED_C") (pintype "bidirectional"))
      (node (ref "IC5") (pin "17") (pinfunction "OUT12_17") (pintype "bidirectional"))
    )
    (net (code "35") (name "Net-(D2-PadA)") (class "Default")
      (node (ref "D2") (pin "A") (pinfunction "A_A") (pintype "passive"))
      (node (ref "L4") (pin "2") (pinfunction "2_2") (pintype "passive"))
    )
    (net (code "36") (name "Net-(D3-PadC)") (class "Default")
      (node (ref "D3") (pin "C") (pinfunction "C_C") (pintype "passive"))
      (node (ref "Q2") (pin "B") (pinfunction "B_B") (pintype "passive"))
      (node (ref "R18") (pin "2") (pinfunction "2_2") (pintype "passive"))
      (node (ref "R23") (pin "2") (pinfunction "2_2") (pintype "passive"))
    )
    (net (code "37") (name "Net-(D4-PadC)") (class "Default")
      (node (ref "D4") (pin "C") (pinfunction "C_C") (pintype "passive"))
      (node (ref "Q3") (pin "B") (pinfunction "B_B") (pintype "passive"))
      (node (ref "R19") (pin "2") (pinfunction "2_2") (pintype "passive"))
      (node (ref "R20") (pin "2") (pinfunction "2_2") (pintype "passive"))
    )
    (net (code "38") (name "Net-(D5-PadC)") (class "Default")
      (node (ref "D5") (pin "C") (pinfunction "C_C") (pintype "passive"))
      (node (ref "Q4") (pin "B") (pinfunction "B_B") (pintype "passive"))
      (node (ref "R21") (pin "2") (pinfunction "2_2") (pintype "passive"))
      (node (ref "R22") (pin "2") (pinfunction "2_2") (pintype "passive"))
    )
    (net (code "39") (name "Net-(IC1-VI)") (class "Default")
      (node (ref "C5") (pin "1") (pinfunction "1_1") (pintype "passive"))
      (node (ref "IC1") (pin "1") (pinfunction "VI_1") (pintype "input"))
      (node (ref "L1") (pin "2") (pinfunction "2_2") (pintype "passive"))
    )
    (net (code "40") (name "Net-(IC2-VI)") (class "Default")
      (node (ref "C3") (pin "1") (pinfunction "1_1") (pintype "passive"))
      (node (ref "IC2") (pin "3") (pinfunction "VI_3") (pintype "input"))
      (node (ref "L2") (pin "1") (pinfunction "1_1") (pintype "passive"))
    )
    (net (code "41") (name "Net-(IC4A-X0)") (class "Default")
      (node (ref "IC4") (pin "13") (pinfunction "X0_13") (pintype "bidirectional"))
      (node (ref "POT_C") (pin "P$2") (pinfunction "S_P$2") (pintype "passive"))
    )
    (net (code "42") (name "Net-(IC4A-X1)") (class "Default")
      (node (ref "IC4") (pin "14") (pinfunction "X1_14") (pintype "bidirectional"))
      (node (ref "SLD_C") (pin "2") (pinfunction "S_2") (pintype "passive"))
    )
    (net (code "43") (name "Net-(IC4A-X2)") (class "Default")
      (node (ref "IC4") (pin "15") (pinfunction "X2_15") (pintype "bidirectional"))
      (node (ref "SLD_B") (pin "2") (pinfunction "S_2") (pintype "passive"))
    )
    (net (code "44") (name "Net-(IC4A-X3)") (class "Default")
      (node (ref "IC4") (pin "12") (pinfunction "X3_12") (pintype "bidirectional"))
      (node (ref "POT_A") (pin "P$2") (pinfunction "S_P$2") (pintype "passive"))
    )
    (net (code "45") (name "Net-(IC4A-X4)") (class "Default")
      (node (ref "IC4") (pin "1") (pinfunction "X4_1") (pintype "bidirectional"))
      (node (ref "SLD_A") (pin "2") (pinfunction "S_2") (pintype "passive"))
    )
    (net (code "46") (name "Net-(IC4A-X6)") (class "Default")
      (node (ref "IC4") (pin "2") (pinfunction "X6_2") (pintype "bidirectional"))
      (node (ref "POT_B") (pin "P$2") (pinfunction "S_P$2") (pintype "passive"))
    )
    (net (code "47") (name "Net-(IC5-IREF)") (class "Default")
      (node (ref "IC5") (pin "23") (pinfunction "IREF_23") (pintype "bidirectional"))
      (node (ref "R5") (pin "1") (pinfunction "1_1") (pintype "passive"))
    )
    (net (code "48") (name "Net-(IC5-OUT1)") (class "Default")
      (node (ref "IC5") (pin "6") (pinfunction "OUT1_6") (pintype "bidirectional"))
      (node (ref "R15") (pin "2") (pinfunction "2_2") (pintype "passive"))
    )
    (net (code "49") (name "Net-(IC5-OUT2)") (class "Default")
      (node (ref "IC5") (pin "7") (pinfunction "OUT2_7") (pintype "bidirectional"))
      (node (ref "MODE_C") (pin "RED_C") (pinfunction "RED_RED_C") (pintype "bidirectional"))
    )
    (net (code "50") (name "Net-(IC5-OUT3)") (class "Default")
      (node (ref "IC5") (pin "8") (pinfunction "OUT3_8") (pintype "bidirectional"))
      (node (ref "MODE_C") (pin "GREEN_C") (pinfunction "GRN_GREEN_C") (pintype "bidirectional"))
    )
    (net (code "51") (name "Net-(IC5-OUT4)") (class "Default")
      (node (ref "IC5") (pin "9") (pinfunction "OUT4_9") (pintype "bidirectional"))
      (node (ref "MODE_A") (pin "GREEN_C") (pinfunction "GRN_GREEN_C") (pintype "bidirectional"))
    )
    (net (code "52") (name "Net-(IC5-OUT5)") (class "Default")
      (node (ref "IC5") (pin "10") (pinfunction "OUT5_10") (pintype "bidirectional"))
      (node (ref "MODE_A") (pin "RED_C") (pinfunction "RED_RED_C") (pintype "bidirectional"))
    )
    (net (code "53") (name "Net-(IC5-OUT6)") (class "Default")
      (node (ref "IC5") (pin "11") (pinfunction "OUT6_11") (pintype "bidirectional"))
      (node (ref "MODE_B") (pin "GREEN_C") (pinfunction "GRN_GREEN_C") (pintype "bidirectional"))
    )
    (net (code "54") (name "Net-(IC5-OUT7)") (class "Default")
      (node (ref "IC5") (pin "12") (pinfunction "OUT7_12") (pintype "bidirectional"))
      (node (ref "MODE_B") (pin "RED_C") (pinfunction "RED_RED_C") (pintype "bidirectional"))
    )
    (net (code "55") (name "Net-(IC5-OUT14)") (class "Default")
      (node (ref "IC5") (pin "19") (pinfunction "OUT14_19") (pintype "bidirectional"))
      (node (ref "R16") (pin "2") (pinfunction "2_2") (pintype "passive"))
    )
    (net (code "56") (name "Net-(IC5-OUT15)") (class "Default")
      (node (ref "IC5") (pin "20") (pinfunction "OUT15_20") (pintype "bidirectional"))
      (node (ref "R17") (pin "2") (pinfunction "2_2") (pintype "passive"))
    )
    (net (code "57") (name "Net-(IC5-VCC)") (class "Default")
      (node (ref "C14") (pin "1") (pinfunction "1_1") (pintype "passive"))
      (node (ref "C15") (pin "1") (pinfunction "1_1") (pintype "passive"))
      (node (ref "IC5") (pin "24") (pinfunction "VCC_24") (pintype "bidirectional"))
      (node (ref "L5") (pin "1") (pinfunction "1_1") (pintype "passive"))
    )
    (net (code "58") (name "Net-(IC6A-+IN)") (class "Default")
      (node (ref "IC6") (pin "3") (pinfunction "+IN_3") (pintype "input"))
      (node (ref "R44") (pin "2") (pinfunction "2_2") (pintype "passive"))
      (node (ref "R47") (pin "1") (pinfunction "1_1") (pintype "passive"))
    )
    (net (code "59") (name "Net-(IC6A--IN)") (class "Default")
      (node (ref "IC6") (pin "2") (pinfunction "-IN_2") (pintype "input"))
      (node (ref "R13") (pin "1") (pinfunction "1_1") (pintype "passive"))
    )
    (net (code "60") (name "Net-(IC6A-OUT)") (class "Default")
      (node (ref "IC6") (pin "1") (pinfunction "OUT_1") (pintype "output"))
      (node (ref "R39") (pin "2") (pinfunction "2_2") (pintype "passive"))
      (node (ref "R44") (pin "1") (pinfunction "1_1") (pintype "passive"))
    )
    (net (code "61") (name "Net-(IC6B-+IN)") (class "Default")
      (node (ref "IC6") (pin "5") (pinfunction "+IN_5") (pintype "input"))
      (node (ref "R41") (pin "2") (pinfunction "2_2") (pintype "passive"))
      (node (ref "R46") (pin "1") (pinfunction "1_1") (pintype "passive"))
    )
    (net (code "62") (name "Net-(IC6B--IN)") (class "Default")
      (node (ref "IC6") (pin "6") (pinfunction "-IN_6") (pintype "input"))
      (node (ref "R12") (pin "1") (pinfunction "1_1") (pintype "passive"))
    )
    (net (code "63") (name "Net-(IC6B-OUT)") (class "Default")
      (node (ref "IC6") (pin "7") (pinfunction "OUT_7") (pintype "output"))
      (node (ref "R38") (pin "2") (pinfunction "2_2") (pintype "passive"))
      (node (ref "R41") (pin "1") (pinfunction "1_1") (pintype "passive"))
    )
    (net (code "64") (name "Net-(IC6C-+IN)") (class "Default")
      (node (ref "IC6") (pin "10") (pinfunction "+IN_10") (pintype "input"))
      (node (ref "R36") (pin "2") (pinfunction "2_2") (pintype "passive"))
      (node (ref "R45") (pin "1") (pinfunction "1_1") (pintype "passive"))
    )
    (net (code "65") (name "Net-(IC6C--IN)") (class "Default")
      (node (ref "IC6") (pin "9") (pinfunction "-IN_9") (pintype "input"))
      (node (ref "R11") (pin "1") (pinfunction "1_1") (pintype "passive"))
    )
    (net (code "66") (name "Net-(IC6C-OUT)") (class "Default")
      (node (ref "IC6") (pin "8") (pinfunction "OUT_8") (pintype "output"))
      (node (ref "R36") (pin "1") (pinfunction "1_1") (pintype "passive"))
      (node (ref "R37") (pin "2") (pinfunction "2_2") (pintype "passive"))
    )
    (net (code "67") (name "Net-(IC6D--IN)") (class "Default")
      (node (ref "IC6") (pin "13") (pinfunction "-IN_13") (pintype "input"))
      (node (ref "IC6") (pin "14") (pinfunction "OUT_14") (pintype "output"))
    )
    (net (code "68") (name "Net-(J4-3)") (class "Default")
      (node (ref "J4") (pin "P3") (pinfunction "3_P3") (pintype "passive"))
      (node (ref "R24") (pin "2") (pinfunction "2_2") (pintype "passive"))
    )
    (net (code "69") (name "Net-(J6-3)") (class "Default")
      (node (ref "J6") (pin "P3") (pinfunction "3_P3") (pintype "passive"))
      (node (ref "R26") (pin "2") (pinfunction "2_2") (pintype "passive"))
    )
    (net (code "70") (name "Net-(J7-3)") (class "Default")
      (node (ref "J7") (pin "P3") (pinfunction "3_P3") (pintype "passive"))
      (node (ref "R37") (pin "1") (pinfunction "1_1") (pintype "passive"))
    )
    (net (code "71") (name "Net-(J8-3)") (class "Default")
      (node (ref "J8") (pin "P3") (pinfunction "3_P3") (pintype "passive"))
      (node (ref "R38") (pin "1") (pinfunction "1_1") (pintype "passive"))
    )
    (net (code "72") (name "Net-(J9-3)") (class "Default")
      (node (ref "J9") (pin "P3") (pinfunction "3_P3") (pintype "passive"))
      (node (ref "R39") (pin "1") (pinfunction "1_1") (pintype "passive"))
    )
    (net (code "73") (name "Net-(J10-3)") (class "Default")
      (node (ref "J10") (pin "P3") (pinfunction "3_P3") (pintype "passive"))
      (node (ref "R35") (pin "1") (pinfunction "1_1") (pintype "passive"))
      (node (ref "R40") (pin "1") (pinfunction "1_1") (pintype "passive"))
    )
    (net (code "74") (name "Net-(J11-3)") (class "Default")
      (node (ref "J11") (pin "P3") (pinfunction "3_P3") (pintype "passive"))
      (node (ref "R29") (pin "1") (pinfunction "1_1") (pintype "passive"))
      (node (ref "R42") (pin "1") (pinfunction "1_1") (pintype "passive"))
    )
    (net (code "75") (name "Net-(J12-3)") (class "Default")
      (node (ref "J12") (pin "P3") (pinfunction "3_P3") (pintype "passive"))
      (node (ref "R32") (pin "1") (pinfunction "1_1") (pintype "passive"))
      (node (ref "R43") (pin "1") (pinfunction "1_1") (pintype "passive"))
    )
    (net (code "76") (name "Net-(Q1B-2)") (class "Default")
      (node (ref "C21") (pin "2") (pinfunction "2_2") (pintype "passive"))
      (node (ref "Q1") (pin "3") (pinfunction "2_3") (pintype "passive"))
      (node (ref "R9") (pin "2") (pinfunction "2_2") (pintype "passive"))
    )
    (net (code "77") (name "Net-(SLD_AA-C)") (class "Default")
      (node (ref "R16") (pin "1") (pinfunction "1_1") (pintype "passive"))
      (node (ref "SLD_A") (pin "E") (pinfunction "C_E") (pintype "passive"))
    )
    (net (code "78") (name "Net-(SLD_BA-C)") (class "Default")
      (node (ref "R17") (pin "1") (pinfunction "1_1") (pintype "passive"))
      (node (ref "SLD_B") (pin "E") (pinfunction "C_E") (pintype "passive"))
    )
    (net (code "79") (name "Net-(SLD_CA-C)") (class "Default")
      (node (ref "R15") (pin "1") (pinfunction "1_1") (pintype "passive"))
      (node (ref "SLD_C") (pin "E") (pinfunction "C_E") (pintype "passive"))
    )
    (net (code "80") (name "Net-(U1-PF0{slash}OSC_IN)") (class "Default")
      (node (ref "R9") (pin "1") (pinfunction "1_1") (pintype "passive"))
      (node (ref "U1") (pin "2") (pinfunction "PF0/OSC_IN_2") (pintype "bidirectional"))
    )
    (net (code "81") (name "Net-(U1-PF1{slash}OSC_OUT)") (class "Default")
      (node (ref "R6") (pin "1") (pinfunction "1_1") (pintype "passive"))
      (node (ref "U1") (pin "3") (pinfunction "PF1/OSC_OUT_3") (pintype "bidirectional"))
    )
    (net (code "82") (name "Net-(U2A--IN)") (class "Default")
      (node (ref "C30") (pin "1") (pinfunction "1_1") (pintype "passive"))
      (node (ref "R14") (pin "2") (pinfunction "2_2") (pintype "passive"))
      (node (ref "R2") (pin "1") (pinfunction "1_1") (pintype "passive"))
      (node (ref "R26") (pin "1") (pinfunction "1_1") (pintype "passive"))
      (node (ref "U2") (pin "2") (pinfunction "-IN_2") (pintype "input"))
    )
    (net (code "83") (name "Net-(U2C--IN)") (class "Default")
      (node (ref "C23") (pin "1") (pinfunction "1_1") (pintype "passive"))
      (node (ref "R25") (pin "1") (pinfunction "1_1") (pintype "passive"))
      (node (ref "R3") (pin "1") (pinfunction "1_1") (pintype "passive"))
      (node (ref "R7") (pin "2") (pinfunction "2_2") (pintype "passive"))
      (node (ref "U2") (pin "9") (pinfunction "-IN_9") (pintype "input"))
    )
    (net (code "84") (name "Net-(U2D--IN)") (class "Default")
      (node (ref "C24") (pin "1") (pinfunction "1_1") (pintype "passive"))
      (node (ref "R24") (pin "1") (pinfunction "1_1") (pintype "passive"))
      (node (ref "R4") (pin "1") (pinfunction "1_1") (pintype "passive"))
      (node (ref "R8") (pin "2") (pinfunction "2_2") (pintype "passive"))
      (node (ref "U2") (pin "13") (pinfunction "-IN_13") (pintype "input"))
    )
    (net (code "85") (name "Net-(U3A--IN)") (class "Default")
      (node (ref "C33") (pin "1") (pinfunction "1_1") (pintype "passive"))
      (node (ref "R30") (pin "1") (pinfunction "1_1") (pintype "passive"))
      (node (ref "R31") (pin "1") (pinfunction "1_1") (pintype "passive"))
      (node (ref "R32") (pin "2") (pinfunction "2_2") (pintype "passive"))
      (node (ref "U3") (pin "2") (pinfunction "-IN_2") (pintype "input"))
    )
    (net (code "86") (name "Net-(U3A-OUT)") (class "Default")
      (node (ref "C33") (pin "2") (pinfunction "2_2") (pintype "passive"))
      (node (ref "R43") (pin "2") (pinfunction "2_2") (pintype "passive"))
      (node (ref "U3") (pin "1") (pinfunction "OUT_1") (pintype "output"))
    )
    (net (code "87") (name "Net-(U3B--IN)") (class "Default")
      (node (ref "C32") (pin "1") (pinfunction "1_1") (pintype "passive"))
      (node (ref "R27") (pin "1") (pinfunction "1_1") (pintype "passive"))
      (node (ref "R28") (pin "1") (pinfunction "1_1") (pintype "passive"))
      (node (ref "R29") (pin "2") (pinfunction "2_2") (pintype "passive"))
      (node (ref "U3") (pin "6") (pinfunction "-IN_6") (pintype "input"))
    )
    (net (code "88") (name "Net-(U3B-OUT)") (class "Default")
      (node (ref "C32") (pin "2") (pinfunction "2_2") (pintype "passive"))
      (node (ref "R42") (pin "2") (pinfunction "2_2") (pintype "passive"))
      (node (ref "U3") (pin "7") (pinfunction "OUT_7") (pintype "output"))
    )
    (net (code "89") (name "Net-(U3C--IN)") (class "Default")
      (node (ref "C34") (pin "1") (pinfunction "1_1") (pintype "passive"))
      (node (ref "R33") (pin "1") (pinfunction "1_1") (pintype "passive"))
      (node (ref "R34") (pin "1") (pinfunction "1_1") (pintype "passive"))
      (node (ref "R35") (pin "2") (pinfunction "2_2") (pintype "passive"))
      (node (ref "U3") (pin "9") (pinfunction "-IN_9") (pintype "input"))
    )
    (net (code "90") (name "Net-(U3C-OUT)") (class "Default")
      (node (ref "C34") (pin "2") (pinfunction "2_2") (pintype "passive"))
      (node (ref "R40") (pin "2") (pinfunction "2_2") (pintype "passive"))
      (node (ref "U3") (pin "8") (pinfunction "OUT_8") (pintype "output"))
    )
    (net (code "91") (name "Net-(U3D--IN)") (class "Default")
      (node (ref "U3") (pin "13") (pinfunction "-IN_13") (pintype "input"))
      (node (ref "U3") (pin "14") (pinfunction "OUT_14") (pintype "output"))
    )
    (net (code "92") (name "POTS_ADDR_A") (class "Default")
      (node (ref "IC4") (pin "11") (pinfunction "A_11") (pintype "input"))
      (node (ref "U1") (pin "13") (pinfunction "PA7_13") (pintype "bidirectional"))
    )
    (net (code "93") (name "POTS_ADDR_B") (class "Default")
      (node (ref "IC4") (pin "10") (pinfunction "B_10") (pintype "input"))
      (node (ref "U1") (pin "18") (pinfunction "PA8_18") (pintype "bidirectional"))
    )
    (net (code "94") (name "POTS_ADDR_C") (class "Default")
      (node (ref "IC4") (pin "9") (pinfunction "C_9") (pintype "input"))
      (node (ref "U1") (pin "19") (pinfunction "PA9_19") (pintype "bidirectional"))
    )
    (net (code "95") (name "RESET") (class "Default")
      (node (ref "C28") (pin "1") (pinfunction "1_1") (pintype "passive"))
      (node (ref "JP2") (pin "4") (pinfunction "4_4") (pintype "passive"))
      (node (ref "R10") (pin "2") (pinfunction "2_2") (pintype "passive"))
      (node (ref "U1") (pin "4") (pinfunction "NRST_4") (pintype "bidirectional"))
    )
    (net (code "96") (name "SWCLK") (class "Default")
      (node (ref "JP2") (pin "3") (pinfunction "3_3") (pintype "passive"))
      (node (ref "U1") (pin "24") (pinfunction "PA14_24") (pintype "bidirectional"))
    )
    (net (code "97") (name "SWDIO") (class "Default")
      (node (ref "JP2") (pin "2") (pinfunction "2_2") (pintype "passive"))
      (node (ref "U1") (pin "23") (pinfunction "PA13_23") (pintype "bidirectional"))
    )
    (net (code "98") (name "SW_MODE_A") (class "Default")
      (node (ref "SW_A") (pin "3") (pinfunction "3_3") (pintype "passive"))
      (node (ref "SW_A") (pin "4") (pinfunction "4_4") (pintype "passive"))
      (node (ref "U1") (pin "27") (pinfunction "PB4_27") (pintype "bidirectional"))
    )
    (net (code "99") (name "SW_MODE_B") (class "Default")
      (node (ref "SW_B") (pin "3") (pinfunction "3_3") (pintype "passive"))
      (node (ref "SW_B") (pin "4") (pinfunction "4_4") (pintype "passive"))
      (node (ref "U1") (pin "29") (pinfunction "PB6_29") (pintype "bidirectional"))
    )
    (net (code "100") (name "SW_MODE_C") (class "Default")
      (node (ref "SW_C") (pin "3") (pinfunction "3_3") (pintype "passive"))
      (node (ref "SW_C") (pin "4") (pinfunction "4_4") (pintype "passive"))
      (node (ref "U1") (pin "30") (pinfunction "PB7_30") (pintype "bidirectional"))
    )
    (net (code "101") (name "VCC") (class "Default")
      (node (ref "C2") (pin "1") (pinfunction "1_1") (pintype "passive"))
      (node (ref "C31") (pin "1") (pinfunction "1_1") (pintype "passive"))
      (node (ref "C35") (pin "1") (pinfunction "1_1") (pintype "passive"))
      (node (ref "C4") (pin "1") (pinfunction "1_1") (pintype "passive"))
      (node (ref "IC6") (pin "4") (pinfunction "V+_4") (pintype "power_in"))
      (node (ref "L3") (pin "1") (pinfunction "1_1") (pintype "passive"))
      (node (ref "U$1") (pin "1") (pinfunction "P$1_1") (pintype "bidirectional"))
      (node (ref "U3") (pin "4") (pinfunction "V+_4") (pintype "power_in"))
    )
    (net (code "102") (name "VEE") (class "Default")
      (node (ref "C10") (pin "2") (pinfunction "2_2") (pintype "passive"))
      (node (ref "C25") (pin "2") (pinfunction "2_2") (pintype "passive"))
      (node (ref "C9") (pin "2") (pinfunction "2_2") (pintype "passive"))
      (node (ref "L4") (pin "1") (pinfunction "1_1") (pintype "passive"))
      (node (ref "R1") (pin "1") (pinfunction "1_1") (pintype "passive"))
      (node (ref "U$1") (pin "2") (pinfunction "P$2_2") (pintype "bidirectional"))
      (node (ref "U3") (pin "11") (pinfunction "V-_11") (pintype "power_in"))
    )
    (net (code "103") (name "unconnected-(IC4A-X5-Pad5)") (class "Default")
      (node (ref "IC4") (pin "5") (pinfunction "X5_5") (pintype "bidirectional"))
    )
    (net (code "104") (name "unconnected-(IC4A-X7-Pad4)") (class "Default")
      (node (ref "IC4") (pin "4") (pinfunction "X7_4") (pintype "bidirectional"))
    )
    (net (code "105") (name "unconnected-(IC5-LAT-Pad4)") (class "Default")
      (node (ref "IC5") (pin "4") (pinfunction "LAT_4") (pintype "bidirectional"))
    )
    (net (code "106") (name "unconnected-(IC5-OUT0-Pad5)") (class "Default")
      (node (ref "IC5") (pin "5") (pinfunction "OUT0_5") (pintype "bidirectional"))
    )
    (net (code "107") (name "unconnected-(IC5-SOUT-Pad22)") (class "Default")
      (node (ref "IC5") (pin "22") (pinfunction "SOUT_22") (pintype "bidirectional"))
    )
    (net (code "108") (name "unconnected-(J7-2-PadP2)") (class "Default")
      (node (ref "J7") (pin "P2") (pinfunction "2_P2") (pintype "passive"))
    )
    (net (code "109") (name "unconnected-(J8-2-PadP2)") (class "Default")
      (node (ref "J8") (pin "P2") (pinfunction "2_P2") (pintype "passive"))
    )
    (net (code "110") (name "unconnected-(J9-2-PadP2)") (class "Default")
      (node (ref "J9") (pin "P2") (pinfunction "2_P2") (pintype "passive"))
    )
    (net (code "111") (name "unconnected-(J10-2-PadP2)") (class "Default")
      (node (ref "J10") (pin "P2") (pinfunction "2_P2") (pintype "passive"))
    )
    (net (code "112") (name "unconnected-(J11-2-PadP2)") (class "Default")
      (node (ref "J11") (pin "P2") (pinfunction "2_P2") (pintype "passive"))
    )
    (net (code "113") (name "unconnected-(J12-2-PadP2)") (class "Default")
      (node (ref "J12") (pin "P2") (pinfunction "2_P2") (pintype "passive"))
    )
  )
)
